# ff555.net
KiCad netlist of a schematic drawn in EAGLE
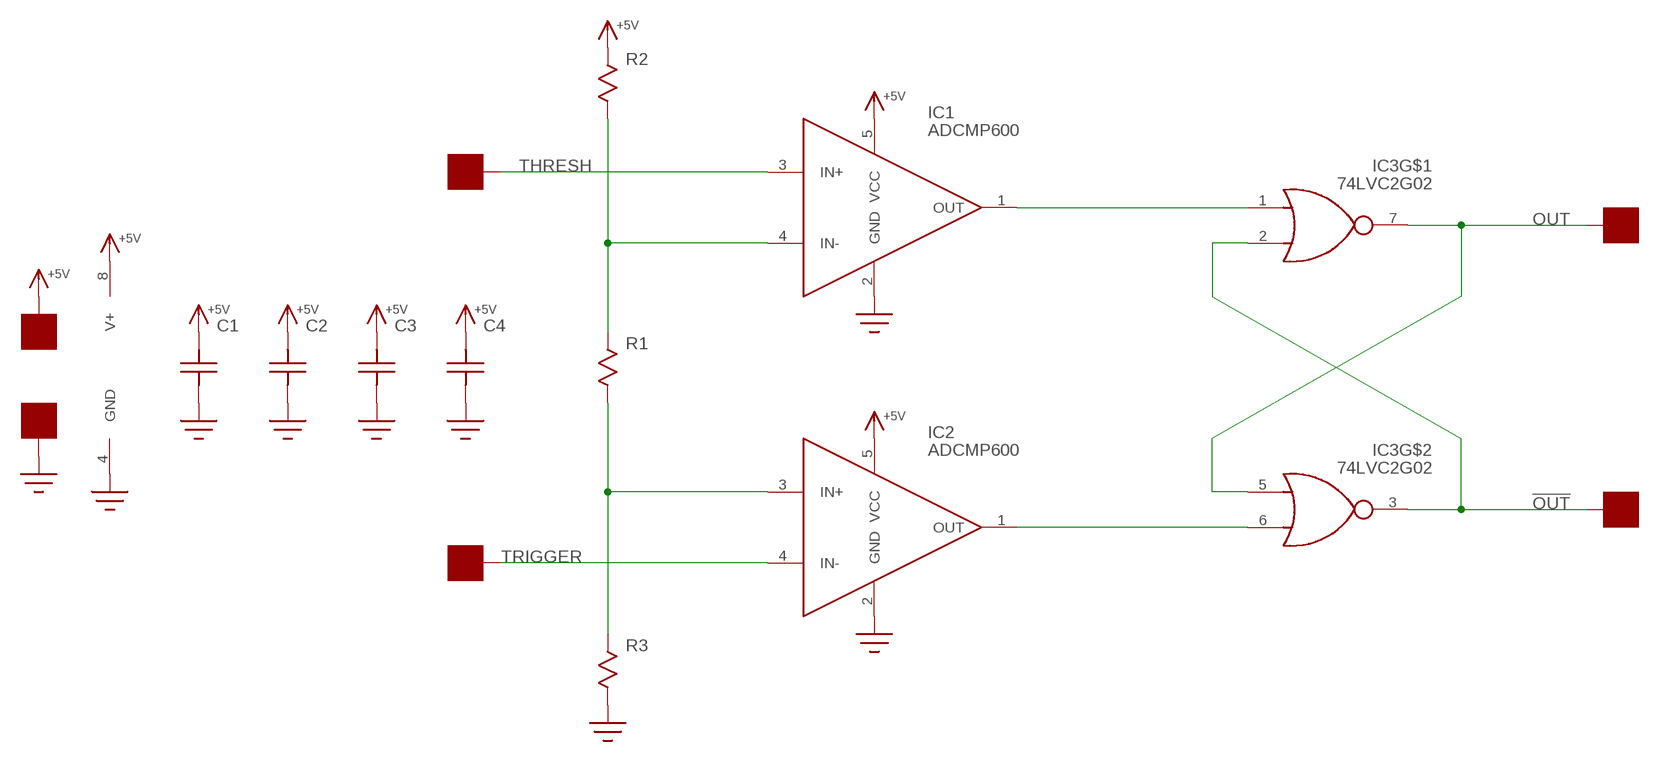
[diagram p0: schematic, sheet 1]

(export (version "E")
  (design (tool "Eeschema 10.0.6"))
  (components
    (comp (ref "C1")
      (value "C0603")
      (footprint "eagle-import:C0603")
      (libsource (lib "eagle-import") (part "C0603"))
    )
    (comp (ref "C2")
      (value "C0603")
      (footprint "eagle-import:C0603")
      (libsource (lib "eagle-import") (part "C0603"))
    )
    (comp (ref "C3")
      (value "C0805")
      (footprint "eagle-import:0805")
      (libsource (lib "eagle-import") (part "C0805"))
    )
    (comp (ref "C4")
      (value "C0603")
      (footprint "eagle-import:C0603")
      (libsource (lib "eagle-import") (part "C0603"))
    )
    (comp (ref "IC1")
      (value "ADCMP600")
      (footprint "eagle-import:SOT23-5")
      (libsource (lib "eagle-import") (part "ADCMP600"))
    )
    (comp (ref "IC2")
      (value "ADCMP600")
      (footprint "eagle-import:SOT23-5")
      (libsource (lib "eagle-import") (part "ADCMP600"))
    )
    (comp (ref "IC3")
      (value "74LVC2G02")
      (footprint "eagle-import:TSSOP8")
      (libsource (lib "eagle-import") (part "74LVC2G02"))
    )
    (comp (ref "R1")
      (value "R0603")
      (footprint "eagle-import:R0603")
      (libsource (lib "eagle-import") (part "R0603"))
    )
    (comp (ref "R2")
      (value "R0603")
      (footprint "eagle-import:R0603")
      (libsource (lib "eagle-import") (part "R0603"))
    )
    (comp (ref "R3")
      (value "R0603")
      (footprint "eagle-import:R0603")
      (libsource (lib "eagle-import") (part "R0603"))
    )
    (comp (ref "U$15")
      (value "PAD100MIL")
      (footprint "eagle-import:PAD_100MIL")
      (libsource (lib "eagle-import") (part "PAD100MIL"))
    )
    (comp (ref "U$16")
      (value "PAD100MIL")
      (footprint "eagle-import:PAD_100MIL")
      (libsource (lib "eagle-import") (part "PAD100MIL"))
    )
    (comp (ref "U$17")
      (value "PAD100MIL")
      (footprint "eagle-import:PAD_100MIL")
      (libsource (lib "eagle-import") (part "PAD100MIL"))
    )
    (comp (ref "U$18")
      (value "PAD100MIL")
      (footprint "eagle-import:PAD_100MIL")
      (libsource (lib "eagle-import") (part "PAD100MIL"))
    )
    (comp (ref "U$19")
      (value "PAD100MIL")
      (footprint "eagle-import:PAD_100MIL")
      (libsource (lib "eagle-import") (part "PAD100MIL"))
    )
    (comp (ref "U$20")
      (value "PAD100MIL")
      (footprint "eagle-import:PAD_100MIL")
      (libsource (lib "eagle-import") (part "PAD100MIL"))
    )
  )
  (nets
    (net (code "1") (name "+5V") (class "Default")
      (node (ref "C1") (pin "P$2") (pinfunction "P$2_P$2") (pintype "bidirectional"))
      (node (ref "C2") (pin "P$2") (pinfunction "P$2_P$2") (pintype "bidirectional"))
      (node (ref "C3") (pin "P$2") (pinfunction "P$2_P$2") (pintype "bidirectional"))
      (node (ref "C4") (pin "P$2") (pinfunction "P$2_P$2") (pintype "bidirectional"))
      (node (ref "IC1") (pin "5") (pinfunction "VCC_5") (pintype "bidirectional"))
      (node (ref "IC2") (pin "5") (pinfunction "VCC_5") (pintype "bidirectional"))
      (node (ref "IC3") (pin "8") (pinfunction "V+_8") (pintype "bidirectional"))
      (node (ref "R2") (pin "P$1") (pinfunction "P$3_P$1") (pintype "bidirectional"))
      (node (ref "U$15") (pin "P$1") (pinfunction "P$1_P$1") (pintype "bidirectional"))
    )
    (net (code "2") (name "/OUT") (class "Default")
      (node (ref "IC3") (pin "5") (pinfunction "A_5") (pintype "bidirectional"))
      (node (ref "IC3") (pin "7") (pinfunction "Y_7") (pintype "bidirectional"))
      (node (ref "U$19") (pin "P$1") (pinfunction "P$1_P$1") (pintype "bidirectional"))
    )
    (net (code "3") (name "/THRESH") (class "Default")
      (node (ref "IC1") (pin "3") (pinfunction "IN+_3") (pintype "bidirectional"))
      (node (ref "U$17") (pin "P$1") (pinfunction "P$1_P$1") (pintype "bidirectional"))
    )
    (net (code "4") (name "/TRIGGER") (class "Default")
      (node (ref "IC2") (pin "4") (pinfunction "IN-_4") (pintype "bidirectional"))
      (node (ref "U$18") (pin "P$1") (pinfunction "P$1_P$1") (pintype "bidirectional"))
    )
    (net (code "5") (name "/~{OUT}") (class "Default")
      (node (ref "IC3") (pin "2") (pinfunction "B_2") (pintype "bidirectional"))
      (node (ref "IC3") (pin "3") (pinfunction "Y_3") (pintype "bidirectional"))
      (node (ref "U$20") (pin "P$1") (pinfunction "P$1_P$1") (pintype "bidirectional"))
    )
    (net (code "6") (name "GND") (class "Default")
      (node (ref "C1") (pin "P$1") (pinfunction "P$1_P$1") (pintype "bidirectional"))
      (node (ref "C2") (pin "P$1") (pinfunction "P$1_P$1") (pintype "bidirectional"))
      (node (ref "C3") (pin "P$1") (pinfunction "P$1_P$1") (pintype "bidirectional"))
      (node (ref "C4") (pin "P$1") (pinfunction "P$1_P$1") (pintype "bidirectional"))
      (node (ref "IC1") (pin "2") (pinfunction "GND_2") (pintype "bidirectional"))
      (node (ref "IC2") (pin "2") (pinfunction "GND_2") (pintype "bidirectional"))
      (node (ref "IC3") (pin "4") (pinfunction "GND_4") (pintype "bidirectional"))
      (node (ref "R3") (pin "P$2") (pinfunction "P$4_P$2") (pintype "bidirectional"))
      (node (ref "U$16") (pin "P$1") (pinfunction "P$1_P$1") (pintype "bidirectional"))
    )
    (net (code "7") (name "Net-(IC1-IN-)") (class "Default")
      (node (ref "IC1") (pin "4") (pinfunction "IN-_4") (pintype "bidirectional"))
      (node (ref "R1") (pin "P$1") (pinfunction "P$3_P$1") (pintype "bidirectional"))
      (node (ref "R2") (pin "P$2") (pinfunction "P$4_P$2") (pintype "bidirectional"))
    )
    (net (code "8") (name "Net-(IC1-OUT)") (class "Default")
      (node (ref "IC1") (pin "1") (pinfunction "OUT_1") (pintype "bidirectional"))
      (node (ref "IC3") (pin "1") (pinfunction "A_1") (pintype "bidirectional"))
    )
    (net (code "9") (name "Net-(IC2-IN+)") (class "Default")
      (node (ref "IC2") (pin "3") (pinfunction "IN+_3") (pintype "bidirectional"))
      (node (ref "R1") (pin "P$2") (pinfunction "P$4_P$2") (pintype "bidirectional"))
      (node (ref "R3") (pin "P$1") (pinfunction "P$3_P$1") (pintype "bidirectional"))
    )
    (net (code "10") (name "Net-(IC2-OUT)") (class "Default")
      (node (ref "IC2") (pin "1") (pinfunction "OUT_1") (pintype "bidirectional"))
      (node (ref "IC3") (pin "6") (pinfunction "B_6") (pintype "bidirectional"))
    )
  )
)
